# usb-io-boardv7.net
KiCad netlist of a schematic drawn in EAGLE
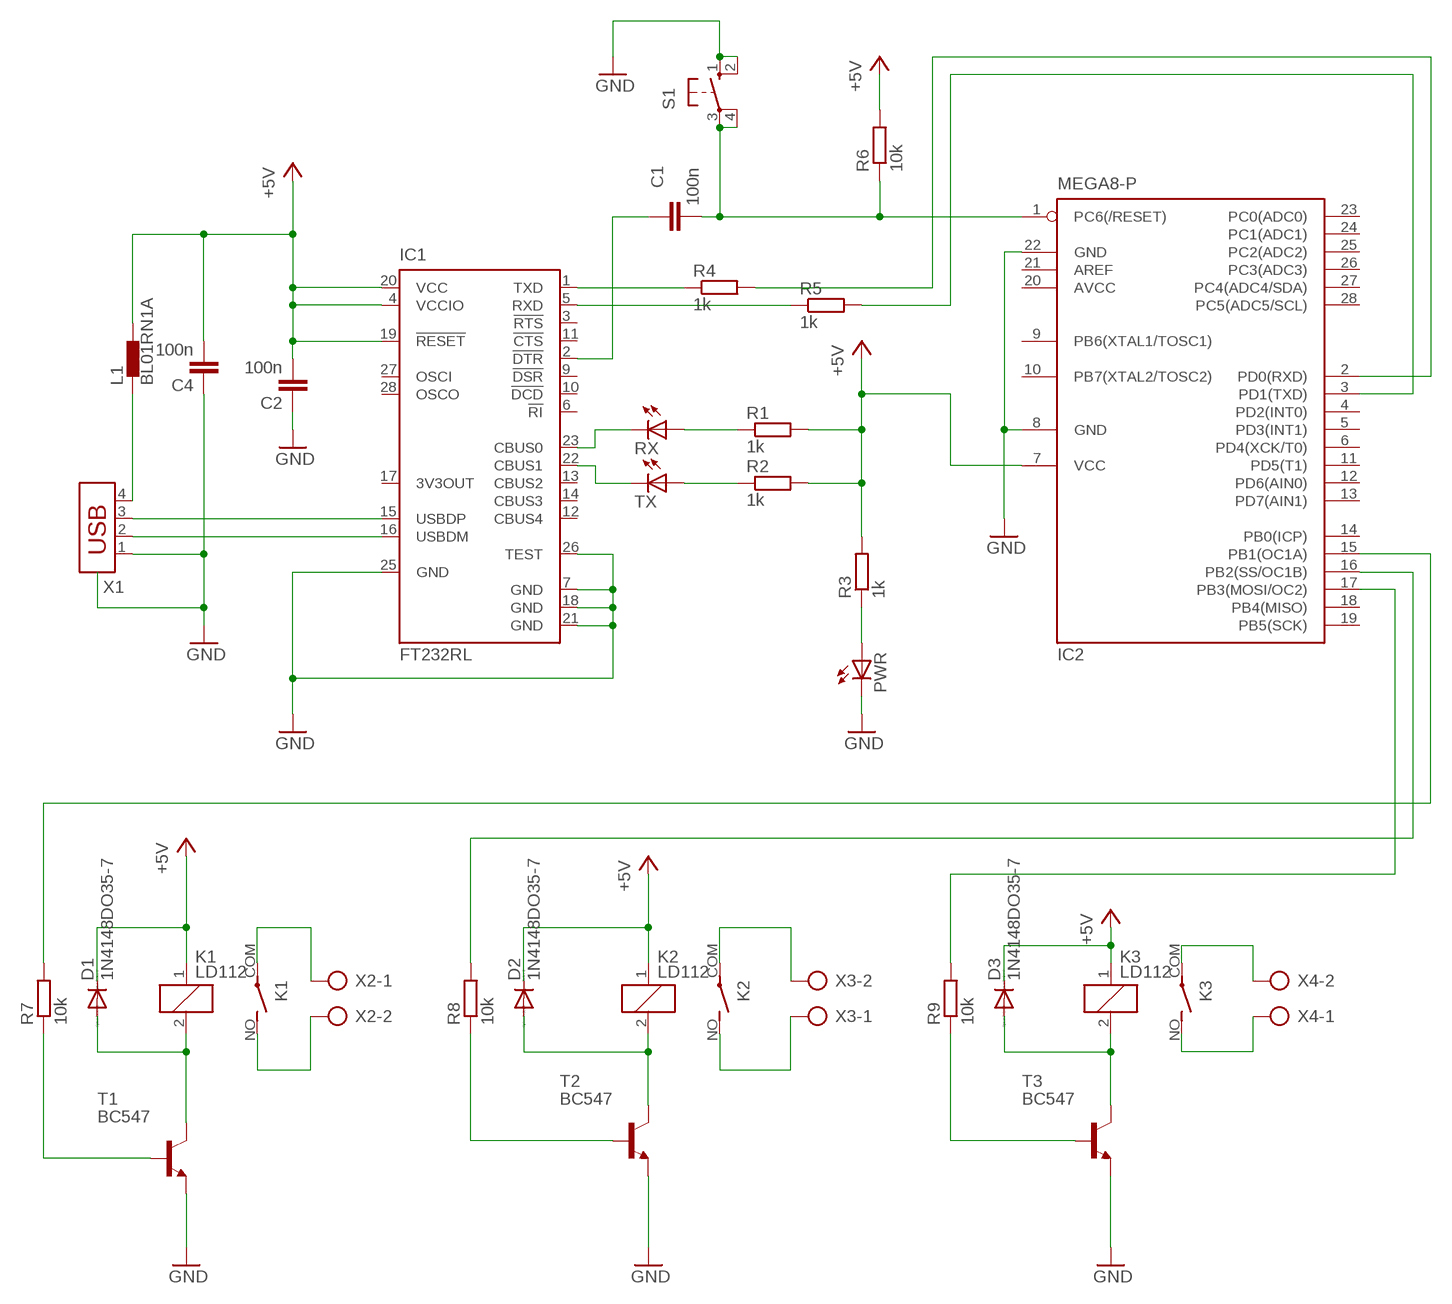
[diagram p0: schematic, sheet 1]

(export (version "E")
  (design (tool "Eeschema 10.0.6"))
  (components
    (comp (ref "C1")
      (value "100n")
      (footprint "eagle-import:C025-024X044")
      (libsource (lib "eagle-import") (part "C-EU025-024X044"))
    )
    (comp (ref "C2")
      (value "100n")
      (footprint "eagle-import:C025-024X044")
      (libsource (lib "eagle-import") (part "C-EU025-024X044"))
    )
    (comp (ref "C4")
      (value "100n")
      (footprint "eagle-import:C025-024X044")
      (libsource (lib "eagle-import") (part "C-EU025-024X044"))
    )
    (comp (ref "D1")
      (value "1N4148DO35-7")
      (footprint "eagle-import:DO35-7")
      (libsource (lib "eagle-import") (part "1N4148DO35-7"))
    )
    (comp (ref "D2")
      (value "1N4148DO35-7")
      (footprint "eagle-import:DO35-7")
      (libsource (lib "eagle-import") (part "1N4148DO35-7"))
    )
    (comp (ref "D3")
      (value "1N4148DO35-7")
      (footprint "eagle-import:DO35-7")
      (libsource (lib "eagle-import") (part "1N4148DO35-7"))
    )
    (comp (ref "IC1")
      (value "FT232RL")
      (footprint "eagle-import:SSOP28")
      (libsource (lib "eagle-import") (part "FT232RL"))
    )
    (comp (ref "IC2")
      (value "MEGA8-P")
      (footprint "eagle-import:DIL28-3")
      (libsource (lib "eagle-import") (part "MEGA8-P"))
    )
    (comp (ref "K1")
      (value "LD112")
      (footprint "eagle-import:LD")
      (fields (field (name "MF") "FARNELL") (field (name "MPN") "ALD112"))
      (libsource (lib "eagle-import") (part "LD?112"))
    )
    (comp (ref "K2")
      (value "LD112")
      (footprint "eagle-import:LD")
      (fields (field (name "MF") "FARNELL") (field (name "MPN") "ALD112"))
      (libsource (lib "eagle-import") (part "LD?112"))
    )
    (comp (ref "K3")
      (value "LD112")
      (footprint "eagle-import:LD")
      (fields (field (name "MF") "FARNELL") (field (name "MPN") "ALD112"))
      (libsource (lib "eagle-import") (part "LD?112"))
    )
    (comp (ref "L1")
      (value "BL01RN1A")
      (footprint "eagle-import:BL01RN1A")
      (libsource (lib "eagle-import") (part "BL01RN1A"))
    )
    (comp (ref "PWR")
      (value "LED5MM")
      (footprint "eagle-import:LED5MM")
      (libsource (lib "eagle-import") (part "LED5MM"))
    )
    (comp (ref "R1")
      (value "1k")
      (footprint "eagle-import:0204_5")
      (libsource (lib "eagle-import") (part "R-EU_0204/5"))
    )
    (comp (ref "R2")
      (value "1k")
      (footprint "eagle-import:0204_5")
      (libsource (lib "eagle-import") (part "R-EU_0204/5"))
    )
    (comp (ref "R3")
      (value "1k")
      (footprint "eagle-import:0204_5")
      (libsource (lib "eagle-import") (part "R-EU_0204/5"))
    )
    (comp (ref "R4")
      (value "1k")
      (footprint "eagle-import:0204_5")
      (libsource (lib "eagle-import") (part "R-EU_0204/5"))
    )
    (comp (ref "R5")
      (value "1k")
      (footprint "eagle-import:0204_5")
      (libsource (lib "eagle-import") (part "R-EU_0204/5"))
    )
    (comp (ref "R6")
      (value "10k")
      (footprint "eagle-import:0204_5")
      (libsource (lib "eagle-import") (part "R-EU_0204/5"))
    )
    (comp (ref "R7")
      (value "10k")
      (footprint "eagle-import:0204_5")
      (libsource (lib "eagle-import") (part "R-EU_0204/5"))
    )
    (comp (ref "R8")
      (value "10k")
      (footprint "eagle-import:0204_5")
      (libsource (lib "eagle-import") (part "R-EU_0204/5"))
    )
    (comp (ref "R9")
      (value "10k")
      (footprint "eagle-import:0204_5")
      (libsource (lib "eagle-import") (part "R-EU_0204/5"))
    )
    (comp (ref "RX")
      (value "LED5MM")
      (footprint "eagle-import:LED5MM")
      (libsource (lib "eagle-import") (part "LED5MM"))
    )
    (comp (ref "S1")
      (value "10-XX")
      (footprint "eagle-import:B3F-10XX")
      (fields (field (name "MPN") "B3F-1000"))
      (libsource (lib "eagle-import") (part "10-XX"))
    )
    (comp (ref "T1")
      (value "BC547")
      (footprint "eagle-import:TO92")
      (libsource (lib "eagle-import") (part "BC547"))
    )
    (comp (ref "T2")
      (value "BC547")
      (footprint "eagle-import:TO92")
      (libsource (lib "eagle-import") (part "BC547"))
    )
    (comp (ref "T3")
      (value "BC547")
      (footprint "eagle-import:TO92")
      (libsource (lib "eagle-import") (part "BC547"))
    )
    (comp (ref "TX")
      (value "LED5MM")
      (footprint "eagle-import:LED5MM")
      (libsource (lib "eagle-import") (part "LED5MM"))
    )
    (comp (ref "X1")
      (value "USB-787616")
      (footprint "eagle-import:USB")
      (libsource (lib "eagle-import") (part "USB-787616"))
    )
    (comp (ref "X2")
      (value "AK500/2")
      (footprint "eagle-import:AK500_2")
      (libsource (lib "eagle-import") (part "AK500/2"))
    )
    (comp (ref "X3")
      (value "AK500/2")
      (footprint "eagle-import:AK500_2")
      (libsource (lib "eagle-import") (part "AK500/2"))
    )
    (comp (ref "X4")
      (value "AK500/2")
      (footprint "eagle-import:AK500_2")
      (libsource (lib "eagle-import") (part "AK500/2"))
    )
  )
  (nets
    (net (code "1") (name "+5V") (class "Default")
      (node (ref "C2") (pin "2") (pinfunction "2_2") (pintype "passive"))
      (node (ref "C4") (pin "2") (pinfunction "2_2") (pintype "passive"))
      (node (ref "D1") (pin "C") (pinfunction "C_C") (pintype "passive"))
      (node (ref "D2") (pin "C") (pinfunction "C_C") (pintype "passive"))
      (node (ref "D3") (pin "C") (pinfunction "C_C") (pintype "passive"))
      (node (ref "IC1") (pin "19") (pinfunction "~{RESET}_19") (pintype "input"))
      (node (ref "IC1") (pin "20") (pinfunction "VCC_20") (pintype "power_in"))
      (node (ref "IC1") (pin "4") (pinfunction "VCCIO_4") (pintype "power_in"))
      (node (ref "IC2") (pin "7") (pinfunction "VCC_7") (pintype "power_in"))
      (node (ref "K1") (pin "1") (pinfunction "1_1") (pintype "passive"))
      (node (ref "K2") (pin "1") (pinfunction "1_1") (pintype "passive"))
      (node (ref "K3") (pin "1") (pinfunction "1_1") (pintype "passive"))
      (node (ref "L1") (pin "2") (pinfunction "2_2") (pintype "passive"))
      (node (ref "R1") (pin "2") (pinfunction "2_2") (pintype "passive"))
      (node (ref "R2") (pin "2") (pinfunction "2_2") (pintype "passive"))
      (node (ref "R3") (pin "2") (pinfunction "2_2") (pintype "passive"))
      (node (ref "R6") (pin "2") (pinfunction "2_2") (pintype "passive"))
    )
    (net (code "2") (name "/AVCC") (class "Default")
      (node (ref "IC2") (pin "20") (pinfunction "AVCC_20") (pintype "power_in"))
    )
    (net (code "3") (name "GND") (class "Default")
      (node (ref "C2") (pin "1") (pinfunction "1_1") (pintype "passive"))
      (node (ref "C4") (pin "1") (pinfunction "1_1") (pintype "passive"))
      (node (ref "IC1") (pin "18") (pinfunction "GND_18") (pintype "power_in"))
      (node (ref "IC1") (pin "21") (pinfunction "GND_21") (pintype "power_in"))
      (node (ref "IC1") (pin "25") (pinfunction "GND_25") (pintype "power_in"))
      (node (ref "IC1") (pin "26") (pinfunction "TEST_26") (pintype "input"))
      (node (ref "IC1") (pin "7") (pinfunction "GND_7") (pintype "power_in"))
      (node (ref "IC2") (pin "22") (pinfunction "GND_22") (pintype "power_in"))
      (node (ref "IC2") (pin "8") (pinfunction "GND_8") (pintype "power_in"))
      (node (ref "PWR") (pin "K") (pinfunction "C_K") (pintype "passive"))
      (node (ref "S1") (pin "1") (pinfunction "S_1") (pintype "passive"))
      (node (ref "S1") (pin "2") (pinfunction "S1_2") (pintype "passive"))
      (node (ref "T1") (pin "1") (pinfunction "E_1") (pintype "passive"))
      (node (ref "T2") (pin "1") (pinfunction "E_1") (pintype "passive"))
      (node (ref "T3") (pin "1") (pinfunction "E_1") (pintype "passive"))
      (node (ref "X1") (pin "1") (pinfunction "1_1") (pintype "passive"))
    )
    (net (code "4") (name "Net-(IC1-CBUS0)") (class "Default")
      (node (ref "IC1") (pin "23") (pinfunction "CBUS0_23") (pintype "bidirectional"))
      (node (ref "RX") (pin "K") (pinfunction "C_K") (pintype "passive"))
    )
    (net (code "5") (name "Net-(IC1-CBUS1)") (class "Default")
      (node (ref "IC1") (pin "22") (pinfunction "CBUS1_22") (pintype "bidirectional"))
      (node (ref "TX") (pin "K") (pinfunction "C_K") (pintype "passive"))
    )
    (net (code "6") (name "Net-(IC1-RXD)") (class "Default")
      (node (ref "IC1") (pin "5") (pinfunction "RXD_5") (pintype "input"))
      (node (ref "R5") (pin "1") (pinfunction "1_1") (pintype "passive"))
    )
    (net (code "7") (name "Net-(IC1-TXD)") (class "Default")
      (node (ref "IC1") (pin "1") (pinfunction "TXD_1") (pintype "output"))
      (node (ref "R4") (pin "1") (pinfunction "1_1") (pintype "passive"))
    )
    (net (code "8") (name "Net-(IC1-USBDM)") (class "Default")
      (node (ref "IC1") (pin "16") (pinfunction "USBDM_16") (pintype "bidirectional"))
      (node (ref "X1") (pin "2") (pinfunction "2_2") (pintype "passive"))
    )
    (net (code "9") (name "Net-(IC1-USBDP)") (class "Default")
      (node (ref "IC1") (pin "15") (pinfunction "USBDP_15") (pintype "bidirectional"))
      (node (ref "X1") (pin "3") (pinfunction "3_3") (pintype "passive"))
    )
    (net (code "10") (name "Net-(IC1-~{DTR})") (class "Default")
      (node (ref "C1") (pin "1") (pinfunction "1_1") (pintype "passive"))
      (node (ref "IC1") (pin "2") (pinfunction "~{DTR}_2") (pintype "output"))
    )
    (net (code "11") (name "Net-(IC2-PB1(OC1A))") (class "Default")
      (node (ref "IC2") (pin "15") (pinfunction "PB1(OC1A)_15") (pintype "bidirectional"))
      (node (ref "R7") (pin "2") (pinfunction "2_2") (pintype "passive"))
    )
    (net (code "12") (name "Net-(IC2-PB2(SS{slash}OC1B))") (class "Default")
      (node (ref "IC2") (pin "16") (pinfunction "PB2(SS/OC1B)_16") (pintype "bidirectional"))
      (node (ref "R8") (pin "2") (pinfunction "2_2") (pintype "passive"))
    )
    (net (code "13") (name "Net-(IC2-PB3(MOSI{slash}OC2))") (class "Default")
      (node (ref "IC2") (pin "17") (pinfunction "PB3(MOSI/OC2)_17") (pintype "bidirectional"))
      (node (ref "R9") (pin "2") (pinfunction "2_2") (pintype "passive"))
    )
    (net (code "14") (name "Net-(IC2-PC6({slash}RESET))") (class "Default")
      (node (ref "C1") (pin "2") (pinfunction "2_2") (pintype "passive"))
      (node (ref "IC2") (pin "1") (pinfunction "PC6(/RESET)_1") (pintype "bidirectional"))
      (node (ref "R6") (pin "1") (pinfunction "1_1") (pintype "passive"))
      (node (ref "S1") (pin "3") (pinfunction "P_3") (pintype "passive"))
      (node (ref "S1") (pin "4") (pinfunction "P1_4") (pintype "passive"))
    )
    (net (code "15") (name "Net-(IC2-PD0(RXD))") (class "Default")
      (node (ref "IC2") (pin "2") (pinfunction "PD0(RXD)_2") (pintype "bidirectional"))
      (node (ref "R4") (pin "2") (pinfunction "2_2") (pintype "passive"))
    )
    (net (code "16") (name "Net-(IC2-PD1(TXD))") (class "Default")
      (node (ref "IC2") (pin "3") (pinfunction "PD1(TXD)_3") (pintype "bidirectional"))
      (node (ref "R5") (pin "2") (pinfunction "2_2") (pintype "passive"))
    )
    (net (code "17") (name "Net-(K1B-P)") (class "Default")
      (node (ref "K1") (pin "COM") (pinfunction "P_COM") (pintype "passive"))
      (node (ref "X2") (pin "1") (pinfunction "KL_1") (pintype "passive"))
    )
    (net (code "18") (name "Net-(K1B-S)") (class "Default")
      (node (ref "K1") (pin "NO") (pinfunction "S_NO") (pintype "passive"))
      (node (ref "X2") (pin "2") (pinfunction "KL_2") (pintype "passive"))
    )
    (net (code "19") (name "Net-(K2B-P)") (class "Default")
      (node (ref "K2") (pin "COM") (pinfunction "P_COM") (pintype "passive"))
      (node (ref "X3") (pin "2") (pinfunction "KL_2") (pintype "passive"))
    )
    (net (code "20") (name "Net-(K2B-S)") (class "Default")
      (node (ref "K2") (pin "NO") (pinfunction "S_NO") (pintype "passive"))
      (node (ref "X3") (pin "1") (pinfunction "KL_1") (pintype "passive"))
    )
    (net (code "21") (name "Net-(K3B-P)") (class "Default")
      (node (ref "K3") (pin "COM") (pinfunction "P_COM") (pintype "passive"))
      (node (ref "X4") (pin "2") (pinfunction "KL_2") (pintype "passive"))
    )
    (net (code "22") (name "Net-(K3B-S)") (class "Default")
      (node (ref "K3") (pin "NO") (pinfunction "S_NO") (pintype "passive"))
      (node (ref "X4") (pin "1") (pinfunction "KL_1") (pintype "passive"))
    )
    (net (code "23") (name "Net-(L1-Pad1)") (class "Default")
      (node (ref "L1") (pin "1") (pinfunction "1_1") (pintype "passive"))
      (node (ref "X1") (pin "4") (pinfunction "4_4") (pintype "passive"))
    )
    (net (code "24") (name "Net-(PWR-PadA)") (class "Default")
      (node (ref "PWR") (pin "A") (pinfunction "A_A") (pintype "passive"))
      (node (ref "R3") (pin "1") (pinfunction "1_1") (pintype "passive"))
    )
    (net (code "25") (name "Net-(R1-Pad1)") (class "Default")
      (node (ref "R1") (pin "1") (pinfunction "1_1") (pintype "passive"))
      (node (ref "RX") (pin "A") (pinfunction "A_A") (pintype "passive"))
    )
    (net (code "26") (name "Net-(R2-Pad1)") (class "Default")
      (node (ref "R2") (pin "1") (pinfunction "1_1") (pintype "passive"))
      (node (ref "TX") (pin "A") (pinfunction "A_A") (pintype "passive"))
    )
    (net (code "27") (name "Net-(T1-B)") (class "Default")
      (node (ref "R7") (pin "1") (pinfunction "1_1") (pintype "passive"))
      (node (ref "T1") (pin "2") (pinfunction "B_2") (pintype "passive"))
    )
    (net (code "28") (name "Net-(T1-C)") (class "Default")
      (node (ref "D1") (pin "A") (pinfunction "A_A") (pintype "passive"))
      (node (ref "K1") (pin "2") (pinfunction "2_2") (pintype "passive"))
      (node (ref "T1") (pin "3") (pinfunction "C_3") (pintype "passive"))
    )
    (net (code "29") (name "Net-(T2-B)") (class "Default")
      (node (ref "R8") (pin "1") (pinfunction "1_1") (pintype "passive"))
      (node (ref "T2") (pin "2") (pinfunction "B_2") (pintype "passive"))
    )
    (net (code "30") (name "Net-(T2-C)") (class "Default")
      (node (ref "D2") (pin "A") (pinfunction "A_A") (pintype "passive"))
      (node (ref "K2") (pin "2") (pinfunction "2_2") (pintype "passive"))
      (node (ref "T2") (pin "3") (pinfunction "C_3") (pintype "passive"))
    )
    (net (code "31") (name "Net-(T3-B)") (class "Default")
      (node (ref "R9") (pin "1") (pinfunction "1_1") (pintype "passive"))
      (node (ref "T3") (pin "2") (pinfunction "B_2") (pintype "passive"))
    )
    (net (code "32") (name "Net-(T3-C)") (class "Default")
      (node (ref "D3") (pin "A") (pinfunction "A_A") (pintype "passive"))
      (node (ref "K3") (pin "2") (pinfunction "2_2") (pintype "passive"))
      (node (ref "T3") (pin "3") (pinfunction "C_3") (pintype "passive"))
    )
    (net (code "33") (name "unconnected-(IC1-3V3OUT-Pad17)") (class "Default")
      (node (ref "IC1") (pin "17") (pinfunction "3V3OUT_17") (pintype "output"))
    )
    (net (code "34") (name "unconnected-(IC1-CBUS2-Pad13)") (class "Default")
      (node (ref "IC1") (pin "13") (pinfunction "CBUS2_13") (pintype "bidirectional"))
    )
    (net (code "35") (name "unconnected-(IC1-CBUS3-Pad14)") (class "Default")
      (node (ref "IC1") (pin "14") (pinfunction "CBUS3_14") (pintype "bidirectional"))
    )
    (net (code "36") (name "unconnected-(IC1-CBUS4-Pad12)") (class "Default")
      (node (ref "IC1") (pin "12") (pinfunction "CBUS4_12") (pintype "bidirectional"))
    )
    (net (code "37") (name "unconnected-(IC1-OSCI-Pad27)") (class "Default")
      (node (ref "IC1") (pin "27") (pinfunction "OSCI_27") (pintype "input"))
    )
    (net (code "38") (name "unconnected-(IC1-OSCO-Pad28)") (class "Default")
      (node (ref "IC1") (pin "28") (pinfunction "OSCO_28") (pintype "output"))
    )
    (net (code "39") (name "unconnected-(IC1-~{CTS}-Pad11)") (class "Default")
      (node (ref "IC1") (pin "11") (pinfunction "~{CTS}_11") (pintype "input"))
    )
    (net (code "40") (name "unconnected-(IC1-~{DCD}-Pad10)") (class "Default")
      (node (ref "IC1") (pin "10") (pinfunction "~{DCD}_10") (pintype "input"))
    )
    (net (code "41") (name "unconnected-(IC1-~{DSR}-Pad9)") (class "Default")
      (node (ref "IC1") (pin "9") (pinfunction "~{DSR}_9") (pintype "input"))
    )
    (net (code "42") (name "unconnected-(IC1-~{RI}-Pad6)") (class "Default")
      (node (ref "IC1") (pin "6") (pinfunction "~{RI}_6") (pintype "input"))
    )
    (net (code "43") (name "unconnected-(IC1-~{RTS}-Pad3)") (class "Default")
      (node (ref "IC1") (pin "3") (pinfunction "~{RTS}_3") (pintype "output"))
    )
    (net (code "44") (name "unconnected-(IC2-AREF-Pad21)") (class "Default")
      (node (ref "IC2") (pin "21") (pinfunction "AREF_21") (pintype "passive"))
    )
    (net (code "45") (name "unconnected-(IC2-PB0(ICP)-Pad14)") (class "Default")
      (node (ref "IC2") (pin "14") (pinfunction "PB0(ICP)_14") (pintype "bidirectional"))
    )
    (net (code "46") (name "unconnected-(IC2-PB4(MISO)-Pad18)") (class "Default")
      (node (ref "IC2") (pin "18") (pinfunction "PB4(MISO)_18") (pintype "bidirectional"))
    )
    (net (code "47") (name "unconnected-(IC2-PB5(SCK)-Pad19)") (class "Default")
      (node (ref "IC2") (pin "19") (pinfunction "PB5(SCK)_19") (pintype "bidirectional"))
    )
    (net (code "48") (name "unconnected-(IC2-PB6(XTAL1{slash}TOSC1)-Pad9)") (class "Default")
      (node (ref "IC2") (pin "9") (pinfunction "PB6(XTAL1/TOSC1)_9") (pintype "bidirectional"))
    )
    (net (code "49") (name "unconnected-(IC2-PB7(XTAL2{slash}TOSC2)-Pad10)") (class "Default")
      (node (ref "IC2") (pin "10") (pinfunction "PB7(XTAL2/TOSC2)_10") (pintype "bidirectional"))
    )
    (net (code "50") (name "unconnected-(IC2-PC0(ADC0)-Pad23)") (class "Default")
      (node (ref "IC2") (pin "23") (pinfunction "PC0(ADC0)_23") (pintype "bidirectional"))
    )
    (net (code "51") (name "unconnected-(IC2-PC1(ADC1)-Pad24)") (class "Default")
      (node (ref "IC2") (pin "24") (pinfunction "PC1(ADC1)_24") (pintype "bidirectional"))
    )
    (net (code "52") (name "unconnected-(IC2-PC2(ADC2)-Pad25)") (class "Default")
      (node (ref "IC2") (pin "25") (pinfunction "PC2(ADC2)_25") (pintype "bidirectional"))
    )
    (net (code "53") (name "unconnected-(IC2-PC3(ADC3)-Pad26)") (class "Default")
      (node (ref "IC2") (pin "26") (pinfunction "PC3(ADC3)_26") (pintype "bidirectional"))
    )
    (net (code "54") (name "unconnected-(IC2-PC4(ADC4{slash}SDA)-Pad27)") (class "Default")
      (node (ref "IC2") (pin "27") (pinfunction "PC4(ADC4/SDA)_27") (pintype "bidirectional"))
    )
    (net (code "55") (name "unconnected-(IC2-PC5(ADC5{slash}SCL)-Pad28)") (class "Default")
      (node (ref "IC2") (pin "28") (pinfunction "PC5(ADC5/SCL)_28") (pintype "bidirectional"))
    )
    (net (code "56") (name "unconnected-(IC2-PD2(INT0)-Pad4)") (class "Default")
      (node (ref "IC2") (pin "4") (pinfunction "PD2(INT0)_4") (pintype "bidirectional"))
    )
    (net (code "57") (name "unconnected-(IC2-PD3(INT1)-Pad5)") (class "Default")
      (node (ref "IC2") (pin "5") (pinfunction "PD3(INT1)_5") (pintype "bidirectional"))
    )
    (net (code "58") (name "unconnected-(IC2-PD4(XCK{slash}T0)-Pad6)") (class "Default")
      (node (ref "IC2") (pin "6") (pinfunction "PD4(XCK/T0)_6") (pintype "bidirectional"))
    )
    (net (code "59") (name "unconnected-(IC2-PD5(T1)-Pad11)") (class "Default")
      (node (ref "IC2") (pin "11") (pinfunction "PD5(T1)_11") (pintype "bidirectional"))
    )
    (net (code "60") (name "unconnected-(IC2-PD6(AIN0)-Pad12)") (class "Default")
      (node (ref "IC2") (pin "12") (pinfunction "PD6(AIN0)_12") (pintype "bidirectional"))
    )
    (net (code "61") (name "unconnected-(IC2-PD7(AIN1)-Pad13)") (class "Default")
      (node (ref "IC2") (pin "13") (pinfunction "PD7(AIN1)_13") (pintype "bidirectional"))
    )
  )
)
